# Regulators.net
KiCad netlist of a schematic drawn in Altium Designer
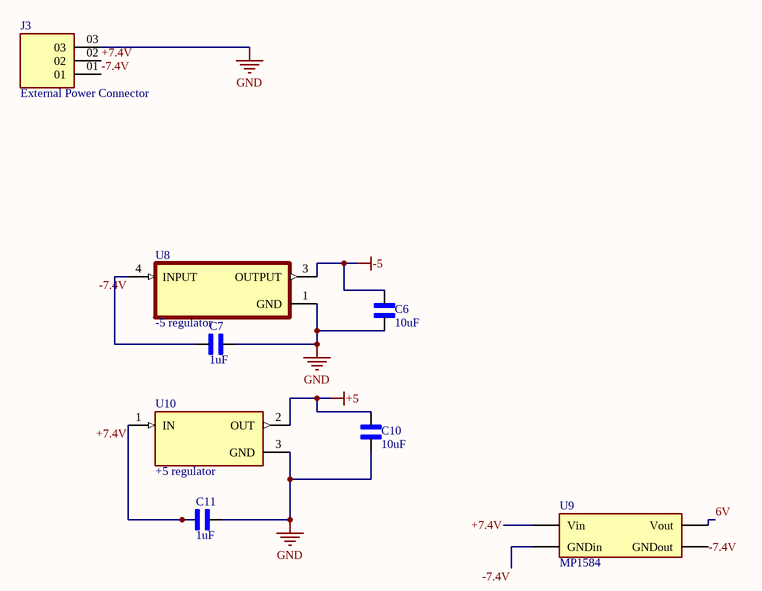
[diagram p0: Regulators.SchDoc]

(export (version "E")
  (design (tool "Eeschema 10.0.6"))
  (components
    (comp (ref "C6")
      (value "10uF")
      (footprint "CAPC2012X135N")
      (description "SMD Capacitor X7R(EIA) with Capacitance: 1.0uF Tol. 10%. Rated Voltage: 25Vdc; GRM21BR71E105KA99L")
      (fields (field (name "MF") "Murata") (field (name "MP") "GRM21BR71E105KA99L"))
      (libsource (lib "") (part "1uF_2"))
    )
    (comp (ref "C7")
      (value "1uF")
      (footprint "CAPC2012X135N")
      (description "SMD Capacitor X7R(EIA) with Capacitance: 1.0uF Tol. 10%. Rated Voltage: 25Vdc; GRM21BR71E105KA99L")
      (fields (field (name "MF") "Murata") (field (name "MP") "GRM21BR71E105KA99L"))
      (libsource (lib "1ufs") (part "1uF"))
    )
    (comp (ref "C10")
      (value "10uF")
      (footprint "CAPC2012X135N")
      (description "SMD Capacitor X7R(EIA) with Capacitance: 1.0uF Tol. 10%. Rated Voltage: 25Vdc; GRM21BR71E105KA99L")
      (fields (field (name "MF") "Murata") (field (name "MP") "GRM21BR71E105KA99L"))
      (libsource (lib "") (part "1uF_1"))
    )
    (comp (ref "C11")
      (value "1uF")
      (footprint "CAPC2012X135N")
      (description "SMD Capacitor X7R(EIA) with Capacitance: 1.0uF Tol. 10%. Rated Voltage: 25Vdc; GRM21BR71E105KA99L")
      (fields (field (name "MF") "Murata") (field (name "MP") "GRM21BR71E105KA99L"))
      (libsource (lib "1ufs") (part "1uF"))
    )
    (comp (ref "J3")
      (value "External Power Connector")
      (footprint "SAMTEC_HTSW-103-XX-X-S")
      (description "HTSW-103-XX-X-S")
      (fields (field (name "MF") "Samtec"))
      (libsource (lib "3 pin connector") (part "HTSW-103-XX-X-S"))
    )
    (comp (ref "U8")
      (value "-5 regulator")
      (footprint "VREG_L7805ACD2T")
      (description "Linear Voltage Regulator IC Negative Fixed 1 Output 1.5A D2PAK; L7905CD2T-TR")
      (fields (field (name "MF") "STMicroelectronics") (field (name "MP") "L7905CD2T-TR"))
      (libsource (lib "-5 regulator") (part "-5 regulator"))
    )
    (comp (ref "U9")
      (value "MP1584")
      (footprint "MP1584")
      (libsource (lib "Integrated_Library_pumchi_musikaya") (part "MP1584"))
    )
    (comp (ref "U10")
      (value "+5 regulator")
      (footprint "TO254P1542X460-3N")
      (description "Linear Voltage Regulator IC Positive Fixed 1 Output 1.5A D2PAK; L7805CD2T-TR")
      (fields (field (name "MF") "STMicroelectronics") (field (name "MP") "L7805CD2T-TR"))
      (libsource (lib "+5 regulator") (part "+5 regulator"))
    )
  )
  (nets
    (net (code "1") (name "+5") (class "Default")
      (node (ref "C10") (pin "2") (pinfunction "2_2") (pintype "passive"))
      (node (ref "U10") (pin "2") (pinfunction "OUT_2") (pintype "output"))
    )
    (net (code "2") (name "-5") (class "Default")
      (node (ref "C6") (pin "1") (pinfunction "1_1") (pintype "passive"))
      (node (ref "U8") (pin "3") (pinfunction "OUTPUT_3") (pintype "output"))
    )
    (net (code "3") (name "/+7.4V") (class "Default")
      (node (ref "C11") (pin "2") (pinfunction "2_2") (pintype "passive"))
      (node (ref "J3") (pin "02") (pinfunction "02_02") (pintype "passive"))
      (node (ref "U10") (pin "1") (pinfunction "IN_1") (pintype "input"))
      (node (ref "U9") (pin "Vin") (pinfunction "Vin_Vin") (pintype "passive"))
    )
    (net (code "4") (name "/-7.4V") (class "Default")
      (node (ref "C7") (pin "2") (pinfunction "2_2") (pintype "passive"))
      (node (ref "J3") (pin "01") (pinfunction "01_01") (pintype "passive"))
      (node (ref "U8") (pin "4") (pinfunction "INPUT_4") (pintype "input"))
      (node (ref "U9") (pin "GNDin") (pinfunction "GNDin_GNDin") (pintype "passive"))
      (node (ref "U9") (pin "GNDout") (pinfunction "GNDout_GNDout") (pintype "passive"))
    )
    (net (code "5") (name "/6V") (class "Default")
      (node (ref "U9") (pin "Vout") (pinfunction "Vout_Vout") (pintype "passive"))
    )
    (net (code "6") (name "GND") (class "Default")
      (node (ref "C10") (pin "1") (pinfunction "1_1") (pintype "passive"))
      (node (ref "C11") (pin "1") (pinfunction "1_1") (pintype "passive"))
      (node (ref "C6") (pin "2") (pinfunction "2_2") (pintype "passive"))
      (node (ref "C7") (pin "1") (pinfunction "1_1") (pintype "passive"))
      (node (ref "J3") (pin "03") (pinfunction "03_03") (pintype "passive"))
      (node (ref "U10") (pin "3") (pinfunction "GND_3") (pintype "power_in"))
      (node (ref "U8") (pin "1") (pinfunction "GND_1") (pintype "power_in"))
    )
  )
)
